# PMIC_Power.net
KiCad netlist of a schematic drawn in Altium Designer
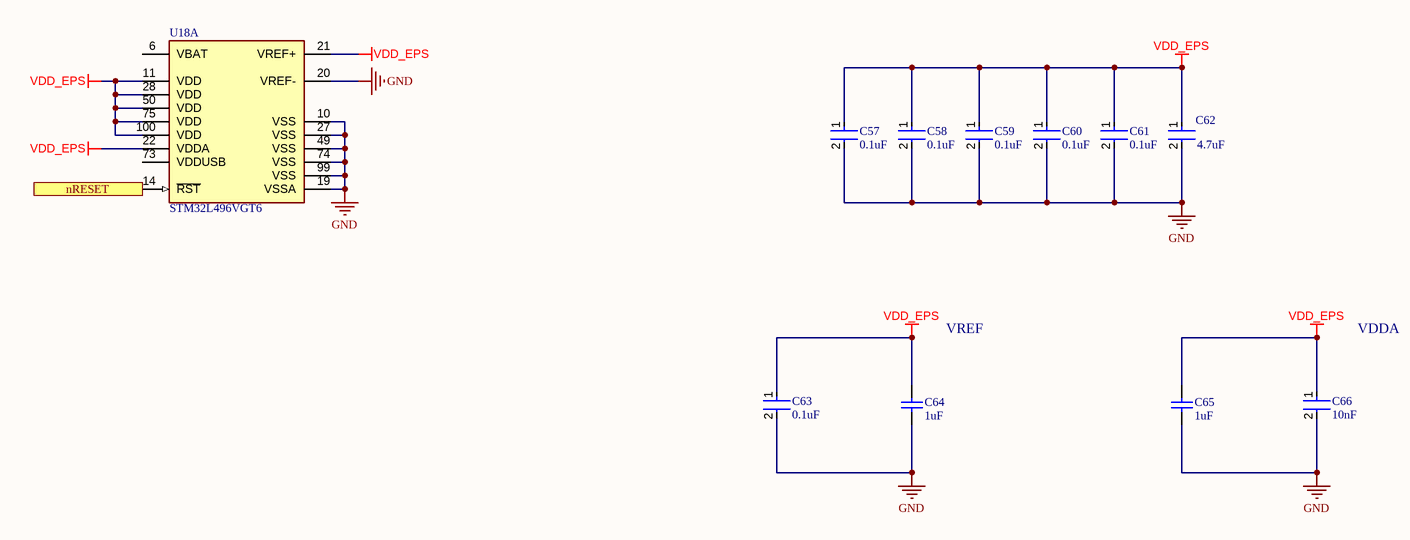
[diagram p0: PMIC_Power.SchDoc]

(export (version "E")
  (design (tool "Eeschema 10.0.6"))
  (components
    (comp (ref "C57")
      (value "0.1uF")
      (footprint "FP-C0603C-CF-MFG")
      (description "CAP CER 0.1UF 50V X7R 0603")
      (fields (field (name "TOLERANCE") "0.1") (field (name "MANUFACTURER") "KEMET"))
      (libsource (lib "Altium Content Vault") (part "b4654b650e69147ec39a6b967a45e02"))
    )
    (comp (ref "C58")
      (value "0.1uF")
      (footprint "FP-C0603C-CF-MFG")
      (description "CAP CER 0.1UF 50V X7R 0603")
      (fields (field (name "TOLERANCE") "0.1") (field (name "MANUFACTURER") "KEMET"))
      (libsource (lib "Altium Content Vault") (part "b4654b650e69147ec39a6b967a45e02"))
    )
    (comp (ref "C59")
      (value "0.1uF")
      (footprint "FP-C0603C-CF-MFG")
      (description "CAP CER 0.1UF 50V X7R 0603")
      (fields (field (name "TOLERANCE") "0.1") (field (name "MANUFACTURER") "KEMET"))
      (libsource (lib "Altium Content Vault") (part "b4654b650e69147ec39a6b967a45e02"))
    )
    (comp (ref "C60")
      (value "0.1uF")
      (footprint "FP-C0603C-CF-MFG")
      (description "CAP CER 0.1UF 50V X7R 0603")
      (fields (field (name "TOLERANCE") "0.1") (field (name "MANUFACTURER") "KEMET"))
      (libsource (lib "Altium Content Vault") (part "b4654b650e69147ec39a6b967a45e02"))
    )
    (comp (ref "C61")
      (value "0.1uF")
      (footprint "FP-C0603C-CF-MFG")
      (description "CAP CER 0.1UF 50V X7R 0603")
      (fields (field (name "TOLERANCE") "0.1") (field (name "MANUFACTURER") "KEMET"))
      (libsource (lib "Altium Content Vault") (part "b4654b650e69147ec39a6b967a45e02"))
    )
    (comp (ref "C62")
      (value "4.7uF")
      (footprint "FP-GRM188-0_15-IPC_A")
      (description "CAP CER 4.7UF 10V X7S 0603")
      (fields (field (name "TOLERANCE") "10%"))
      (libsource (lib "Altium Content Vault") (part "02cd4be3c70576c341d710602a673aa"))
    )
    (comp (ref "C63")
      (value "0.1uF")
      (footprint "FP-C0603C-CF-MFG")
      (description "CAP CER 0.1UF 50V X7R 0603")
      (fields (field (name "TOLERANCE") "0.1") (field (name "MANUFACTURER") "KEMET"))
      (libsource (lib "Altium Content Vault") (part "b4654b650e69147ec39a6b967a45e02"))
    )
    (comp (ref "C64")
      (value "1uF")
      (footprint "CAPC1608X90X35LL15T15")
      (fields (field (name "MANUFACTURER") "Kemet") (field (name "PART NUMBER") "C0603C105K4RACTU"))
      (libsource (lib "Altium Content Vault") (part "CAP"))
    )
    (comp (ref "C65")
      (value "1uF")
      (footprint "CAPC1608X90X35LL15T15")
      (fields (field (name "MANUFACTURER") "Kemet") (field (name "PART NUMBER") "C0603C105K4RACTU"))
      (libsource (lib "Altium Content Vault") (part "CAP"))
    )
    (comp (ref "C66")
      (value "10nF")
      (footprint "FP-GRM188-0_1-e0_2_0_5-IPC_A")
      (description "Chip Multilayer Ceramic Capacitors for General Purpose, 0603, 10000pF, X7R, 15%, 10%, 100V")
      (fields (field (name "VOLTAGE") "100V") (field (name "TOLERANCE") "10%"))
      (libsource (lib "Altium Content Vault") (part "11868f565c42a9108669ba33697ecf6"))
    )
    (comp (ref "U18")
      (value "STM32L496VGT6")
      (footprint "FP-LQFP100-1L-MFG")
      (description "IC MCU 32BIT 1MB FLASH 100LQFP")
      (fields
        (field (name "MANUFACTURER") "STMicroelectronics")
        (field (name "OCTOPART") "https://octopart.com/stm32l496vgt6-stmicroelectronics-80826723")
      )
      (libsource (lib "Altium Content Vault") (part "c3654b0af0513536dfc3423c68ccd0e"))
    )
  )
  (nets
    (net (code "1") (name "/nRESET") (class "Default")
      (node (ref "U18") (pin "14") (pinfunction "~{RST}_14") (pintype "input"))
    )
    (net (code "2") (name "GND") (class "Default")
      (node (ref "C57") (pin "2") (pinfunction "2_2") (pintype "passive"))
      (node (ref "C58") (pin "2") (pinfunction "2_2") (pintype "passive"))
      (node (ref "C59") (pin "2") (pinfunction "2_2") (pintype "passive"))
      (node (ref "C60") (pin "2") (pinfunction "2_2") (pintype "passive"))
      (node (ref "C61") (pin "2") (pinfunction "2_2") (pintype "passive"))
      (node (ref "C62") (pin "2") (pinfunction "2_2") (pintype "passive"))
      (node (ref "C63") (pin "2") (pinfunction "2_2") (pintype "passive"))
      (node (ref "C64") (pin "1") (pinfunction "1_1") (pintype "passive"))
      (node (ref "C65") (pin "1") (pinfunction "1_1") (pintype "passive"))
      (node (ref "C66") (pin "2") (pinfunction "2_2") (pintype "passive"))
      (node (ref "U18") (pin "10") (pinfunction "VSS_10") (pintype "power_in"))
      (node (ref "U18") (pin "19") (pinfunction "VSSA_19") (pintype "power_in"))
      (node (ref "U18") (pin "20") (pinfunction "VREF-_20") (pintype "power_in"))
      (node (ref "U18") (pin "27") (pinfunction "VSS_27") (pintype "power_in"))
      (node (ref "U18") (pin "49") (pinfunction "VSS_49") (pintype "power_in"))
      (node (ref "U18") (pin "74") (pinfunction "VSS_74") (pintype "power_in"))
      (node (ref "U18") (pin "99") (pinfunction "VSS_99") (pintype "power_in"))
    )
    (net (code "3") (name "VDD_EPS") (class "Default")
      (node (ref "C57") (pin "1") (pinfunction "1_1") (pintype "passive"))
      (node (ref "C58") (pin "1") (pinfunction "1_1") (pintype "passive"))
      (node (ref "C59") (pin "1") (pinfunction "1_1") (pintype "passive"))
      (node (ref "C60") (pin "1") (pinfunction "1_1") (pintype "passive"))
      (node (ref "C61") (pin "1") (pinfunction "1_1") (pintype "passive"))
      (node (ref "C62") (pin "1") (pinfunction "1_1") (pintype "passive"))
      (node (ref "C63") (pin "1") (pinfunction "1_1") (pintype "passive"))
      (node (ref "C64") (pin "2") (pinfunction "2_2") (pintype "passive"))
      (node (ref "C65") (pin "2") (pinfunction "2_2") (pintype "passive"))
      (node (ref "C66") (pin "1") (pinfunction "1_1") (pintype "passive"))
      (node (ref "U18") (pin "100") (pinfunction "VDD_100") (pintype "power_in"))
      (node (ref "U18") (pin "11") (pinfunction "VDD_11") (pintype "power_in"))
      (node (ref "U18") (pin "21") (pinfunction "VREF+_21") (pintype "power_in"))
      (node (ref "U18") (pin "22") (pinfunction "VDDA_22") (pintype "power_in"))
      (node (ref "U18") (pin "28") (pinfunction "VDD_28") (pintype "power_in"))
      (node (ref "U18") (pin "50") (pinfunction "VDD_50") (pintype "power_in"))
      (node (ref "U18") (pin "75") (pinfunction "VDD_75") (pintype "power_in"))
    )
    (net (code "4") (name "unconnected-(U18A-VBAT-Pad6)") (class "Default")
      (node (ref "U18") (pin "6") (pinfunction "VBAT_6") (pintype "power_in"))
    )
    (net (code "5") (name "unconnected-(U18A-VDDUSB-Pad73)") (class "Default")
      (node (ref "U18") (pin "73") (pinfunction "VDDUSB_73") (pintype "power_in"))
    )
  )
)
